# Inverter_3_Phase_MC3PHAC.net
KiCad netlist of a schematic drawn in EAGLE
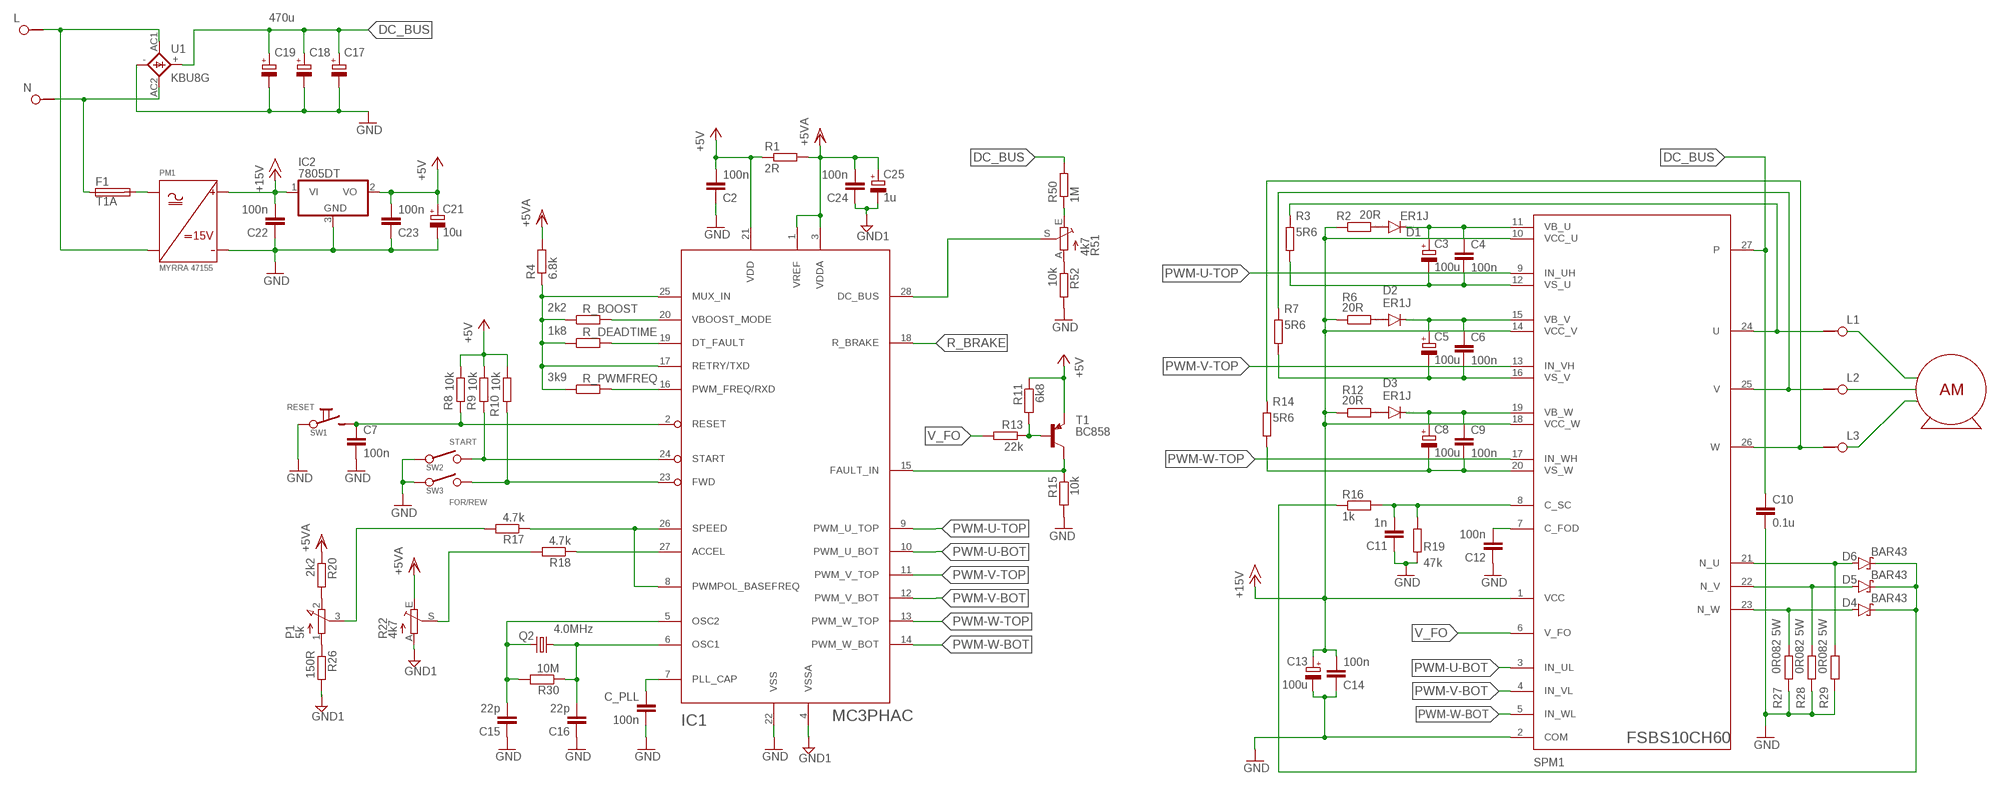
[diagram p0: schematic, sheet 1]

(export (version "E")
  (design (tool "Eeschema 10.0.6"))
  (components
    (comp (ref "C2")
      (value "100n")
      (footprint "eagle-import:C0805")
      (libsource (lib "eagle-import") (part "C-EUC0805"))
    )
    (comp (ref "C3")
      (value "100u")
      (footprint "eagle-import:E2,5-7")
      (libsource (lib "eagle-import") (part "CPOL-EUE2.5-7"))
    )
    (comp (ref "C4")
      (value "100n")
      (footprint "eagle-import:C0805")
      (libsource (lib "eagle-import") (part "C-EUC0805"))
    )
    (comp (ref "C5")
      (value "100u")
      (footprint "eagle-import:E2,5-7")
      (libsource (lib "eagle-import") (part "CPOL-EUE2.5-7"))
    )
    (comp (ref "C6")
      (value "100n")
      (footprint "eagle-import:C0805")
      (libsource (lib "eagle-import") (part "C-EUC0805"))
    )
    (comp (ref "C7")
      (value "100n")
      (footprint "eagle-import:C0805")
      (libsource (lib "eagle-import") (part "C-EUC0805"))
    )
    (comp (ref "C8")
      (value "100u")
      (footprint "eagle-import:E2,5-7")
      (libsource (lib "eagle-import") (part "CPOL-EUE2.5-7"))
    )
    (comp (ref "C9")
      (value "100n")
      (footprint "eagle-import:C0805")
      (libsource (lib "eagle-import") (part "C-EUC0805"))
    )
    (comp (ref "C10")
      (value "0.1u")
      (footprint "eagle-import:C225-074X268")
      (libsource (lib "eagle-import") (part "C-EU225-074X268"))
    )
    (comp (ref "C11")
      (value "1n")
      (footprint "eagle-import:C0805")
      (libsource (lib "eagle-import") (part "C-EUC0805"))
    )
    (comp (ref "C12")
      (value "100n")
      (footprint "eagle-import:C0805")
      (libsource (lib "eagle-import") (part "C-EUC0805"))
    )
    (comp (ref "C13")
      (value "100u")
      (footprint "eagle-import:E2,5-7")
      (libsource (lib "eagle-import") (part "CPOL-EUE2.5-7"))
    )
    (comp (ref "C14")
      (value "100n")
      (footprint "eagle-import:C0805")
      (libsource (lib "eagle-import") (part "C-EUC0805"))
    )
    (comp (ref "C15")
      (value "22p")
      (footprint "eagle-import:C0805")
      (libsource (lib "eagle-import") (part "C-EUC0805"))
    )
    (comp (ref "C16")
      (value "22p")
      (footprint "eagle-import:C0805")
      (libsource (lib "eagle-import") (part "C-EUC0805"))
    )
    (comp (ref "C17")
      (value "470u")
      (footprint "eagle-import:EB35D")
      (libsource (lib "eagle-import") (part "CPOL-EUE10-35"))
    )
    (comp (ref "C18")
      (value "470u")
      (footprint "eagle-import:EB35D")
      (libsource (lib "eagle-import") (part "CPOL-EUE10-35"))
    )
    (comp (ref "C19")
      (value "470u")
      (footprint "eagle-import:EB35D")
      (libsource (lib "eagle-import") (part "CPOL-EUE10-35"))
    )
    (comp (ref "C21")
      (value "10u")
      (footprint "eagle-import:E2,5-7")
      (libsource (lib "eagle-import") (part "CPOL-EUE2.5-7"))
    )
    (comp (ref "C22")
      (value "100n")
      (footprint "eagle-import:C0805")
      (libsource (lib "eagle-import") (part "C-EUC0805"))
    )
    (comp (ref "C23")
      (value "100n")
      (footprint "eagle-import:C0805")
      (libsource (lib "eagle-import") (part "C-EUC0805"))
    )
    (comp (ref "C24")
      (value "100n")
      (footprint "eagle-import:C0805")
      (libsource (lib "eagle-import") (part "C-EUC0805"))
    )
    (comp (ref "C25")
      (value "1u")
      (footprint "eagle-import:E2,5-7")
      (libsource (lib "eagle-import") (part "CPOL-EUE2.5-7"))
    )
    (comp (ref "C_PLL")
      (value "100n")
      (footprint "eagle-import:C0805")
      (libsource (lib "eagle-import") (part "C-EUC0805"))
    )
    (comp (ref "D1")
      (value "ER1J")
      (footprint "eagle-import:DO214AC")
      (libsource (lib "eagle-import") (part "DIODE-DO214AC"))
    )
    (comp (ref "D2")
      (value "ER1J")
      (footprint "eagle-import:DO214AC")
      (libsource (lib "eagle-import") (part "DIODE-DO214AC"))
    )
    (comp (ref "D3")
      (value "ER1J")
      (footprint "eagle-import:DO214AC")
      (libsource (lib "eagle-import") (part "DIODE-DO214AC"))
    )
    (comp (ref "D4")
      (value "BAR43")
      (footprint "eagle-import:SOT23")
      (libsource (lib "eagle-import") (part "BAT54"))
    )
    (comp (ref "D5")
      (value "BAR43")
      (footprint "eagle-import:SOT23")
      (libsource (lib "eagle-import") (part "BAT54"))
    )
    (comp (ref "D6")
      (value "BAR43")
      (footprint "eagle-import:SOT23")
      (libsource (lib "eagle-import") (part "BAT54"))
    )
    (comp (ref "F1")
      (value "T1A")
      (footprint "eagle-import:SH22,5")
      (libsource (lib "eagle-import") (part "FUSESH22,5"))
    )
    (comp (ref "IC1")
      (value "MC3PHAC")
      (footprint "eagle-import:SO28W")
      (libsource (lib "eagle-import") (part "MC3PHAC"))
    )
    (comp (ref "IC2")
      (value "7805DT")
      (footprint "eagle-import:TO252")
      (libsource (lib "eagle-import") (part "78DT05"))
    )
    (comp (ref "L")
      (value "L")
      (footprint "eagle-import:W236-1")
      (libsource (lib "eagle-import") (part "W236-1"))
    )
    (comp (ref "L1")
      (value "L1")
      (footprint "eagle-import:W236-1")
      (libsource (lib "eagle-import") (part "W236-1"))
    )
    (comp (ref "L2")
      (value "L2")
      (footprint "eagle-import:W236-1")
      (libsource (lib "eagle-import") (part "W236-1"))
    )
    (comp (ref "L3")
      (value "L3")
      (footprint "eagle-import:W236-1")
      (libsource (lib "eagle-import") (part "W236-1"))
    )
    (comp (ref "N")
      (value "N")
      (footprint "eagle-import:W236-1")
      (libsource (lib "eagle-import") (part "W236-1"))
    )
    (comp (ref "P1")
      (value "5k")
      (footprint "eagle-import:1X03")
      (libsource (lib "eagle-import") (part "POT"))
    )
    (comp (ref "PM1")
      (value "MYRRA 47155")
      (footprint "eagle-import:MYRRA")
      (libsource (lib "eagle-import") (part "MYRRA"))
    )
    (comp (ref "Q2")
      (value "4.0MHz")
      (footprint "eagle-import:HC49U-V")
      (libsource (lib "eagle-import") (part "CRYSTALHC49U-V"))
    )
    (comp (ref "R1")
      (value "2R")
      (footprint "eagle-import:R1206")
      (libsource (lib "eagle-import") (part "R-EU_R1206"))
    )
    (comp (ref "R2")
      (value "20R")
      (footprint "eagle-import:R1206")
      (libsource (lib "eagle-import") (part "R-EU_R1206"))
    )
    (comp (ref "R3")
      (value "5R6")
      (footprint "eagle-import:M1206")
      (libsource (lib "eagle-import") (part "R-EU_M1206"))
    )
    (comp (ref "R4")
      (value "6.8k")
      (footprint "eagle-import:R0805")
      (libsource (lib "eagle-import") (part "R-EU_R0805"))
    )
    (comp (ref "R6")
      (value "20R")
      (footprint "eagle-import:R1206")
      (libsource (lib "eagle-import") (part "R-EU_R1206"))
    )
    (comp (ref "R7")
      (value "5R6")
      (footprint "eagle-import:M1206")
      (libsource (lib "eagle-import") (part "R-EU_M1206"))
    )
    (comp (ref "R8")
      (value "10k")
      (footprint "eagle-import:R0805")
      (libsource (lib "eagle-import") (part "R-EU_R0805"))
    )
    (comp (ref "R9")
      (value "10k")
      (footprint "eagle-import:R0805")
      (libsource (lib "eagle-import") (part "R-EU_R0805"))
    )
    (comp (ref "R10")
      (value "10k")
      (footprint "eagle-import:R1206")
      (libsource (lib "eagle-import") (part "R-EU_R1206"))
    )
    (comp (ref "R11")
      (value "6k8")
      (footprint "eagle-import:R0805")
      (libsource (lib "eagle-import") (part "R-EU_R0805"))
    )
    (comp (ref "R12")
      (value "20R")
      (footprint "eagle-import:R1206")
      (libsource (lib "eagle-import") (part "R-EU_R1206"))
    )
    (comp (ref "R13")
      (value "22k")
      (footprint "eagle-import:R0805")
      (libsource (lib "eagle-import") (part "R-EU_R0805"))
    )
    (comp (ref "R14")
      (value "5R6")
      (footprint "eagle-import:M1206")
      (libsource (lib "eagle-import") (part "R-EU_M1206"))
    )
    (comp (ref "R15")
      (value "10k")
      (footprint "eagle-import:R0805")
      (libsource (lib "eagle-import") (part "R-EU_R0805"))
    )
    (comp (ref "R16")
      (value "1k")
      (footprint "eagle-import:R0805")
      (libsource (lib "eagle-import") (part "R-EU_R0805"))
    )
    (comp (ref "R17")
      (value "4.7k")
      (footprint "eagle-import:R0805")
      (libsource (lib "eagle-import") (part "R-EU_R0805"))
    )
    (comp (ref "R18")
      (value "4.7k")
      (footprint "eagle-import:R0805")
      (libsource (lib "eagle-import") (part "R-EU_R0805"))
    )
    (comp (ref "R19")
      (value "47k")
      (footprint "eagle-import:R0805")
      (libsource (lib "eagle-import") (part "R-EU_R0805"))
    )
    (comp (ref "R20")
      (value "2k2")
      (footprint "eagle-import:R0805")
      (libsource (lib "eagle-import") (part "R-EU_R0805"))
    )
    (comp (ref "R22")
      (value "4k7")
      (footprint "eagle-import:CA9V")
      (libsource (lib "eagle-import") (part "TRIM_EU-CA9V"))
    )
    (comp (ref "R26")
      (value "150R")
      (footprint "eagle-import:R0805")
      (libsource (lib "eagle-import") (part "R-EU_R0805"))
    )
    (comp (ref "R27")
      (value "0R082 5W")
      (footprint "eagle-import:WSC4527")
      (libsource (lib "eagle-import") (part "R-EU_WSC4527"))
    )
    (comp (ref "R28")
      (value "0R082 5W")
      (footprint "eagle-import:WSC4527")
      (libsource (lib "eagle-import") (part "R-EU_WSC4527"))
    )
    (comp (ref "R29")
      (value "0R082 5W")
      (footprint "eagle-import:WSC4527")
      (libsource (lib "eagle-import") (part "R-EU_WSC4527"))
    )
    (comp (ref "R30")
      (value "10M")
      (footprint "eagle-import:R0805")
      (libsource (lib "eagle-import") (part "R-EU_R0805"))
    )
    (comp (ref "R50")
      (value "1M")
      (footprint "eagle-import:0207_10")
      (libsource (lib "eagle-import") (part "R-EU_0207/10"))
    )
    (comp (ref "R51")
      (value "4k7")
      (footprint "eagle-import:CA9V")
      (libsource (lib "eagle-import") (part "TRIM_EU-CA9V"))
    )
    (comp (ref "R52")
      (value "10k")
      (footprint "eagle-import:R0805")
      (libsource (lib "eagle-import") (part "R-EU_R0805"))
    )
    (comp (ref "R_BOOST")
      (value "2k2")
      (footprint "eagle-import:R0805")
      (libsource (lib "eagle-import") (part "R-EU_R0805"))
    )
    (comp (ref "R_DEADTIME")
      (value "1k8")
      (footprint "eagle-import:R0805")
      (libsource (lib "eagle-import") (part "R-EU_R0805"))
    )
    (comp (ref "R_PWMFREQ")
      (value "3k9")
      (footprint "eagle-import:R0805")
      (libsource (lib "eagle-import") (part "R-EU_R0805"))
    )
    (comp (ref "SPM1")
      (value "FSBS10CH60")
      (footprint "eagle-import:SPM27-BA")
      (libsource (lib "eagle-import") (part "FSBS10CH60"))
    )
    (comp (ref "SW1")
      (value "RESET")
      (footprint "eagle-import:1X02")
      (libsource (lib "eagle-import") (part "BUTTON"))
    )
    (comp (ref "SW2")
      (value "START")
      (footprint "eagle-import:1X02")
      (libsource (lib "eagle-import") (part "SWITCH"))
    )
    (comp (ref "SW3")
      (value "FOR/REW")
      (footprint "eagle-import:1X02")
      (libsource (lib "eagle-import") (part "SWITCH"))
    )
    (comp (ref "T1")
      (value "BC858")
      (footprint "eagle-import:SOT23-BEC")
      (libsource (lib "eagle-import") (part "-PNP-SOT23-BECBC856B"))
    )
    (comp (ref "U1")
      (value "KBU8G")
      (footprint "eagle-import:KBU")
      (libsource (lib "eagle-import") (part "KBU"))
    )
  )
  (nets
    (net (code "1") (name "+5V") (class "Default")
      (node (ref "C2") (pin "2") (pinfunction "2_2") (pintype "passive"))
      (node (ref "C21") (pin "+") (pinfunction "+_+") (pintype "passive"))
      (node (ref "C23") (pin "2") (pinfunction "2_2") (pintype "passive"))
      (node (ref "IC1") (pin "21") (pinfunction "VDD_21") (pintype "power_in"))
      (node (ref "IC2") (pin "2") (pinfunction "VO_2") (pintype "passive"))
      (node (ref "R1") (pin "2") (pinfunction "2_2") (pintype "passive"))
      (node (ref "R10") (pin "1") (pinfunction "1_1") (pintype "passive"))
      (node (ref "R11") (pin "1") (pinfunction "1_1") (pintype "passive"))
      (node (ref "R8") (pin "1") (pinfunction "1_1") (pintype "passive"))
      (node (ref "R9") (pin "1") (pinfunction "1_1") (pintype "passive"))
      (node (ref "T1") (pin "E") (pinfunction "E_E") (pintype "passive"))
    )
    (net (code "2") (name "+5VA") (class "Default")
      (node (ref "C24") (pin "2") (pinfunction "2_2") (pintype "passive"))
      (node (ref "C25") (pin "+") (pinfunction "+_+") (pintype "passive"))
      (node (ref "IC1") (pin "1") (pinfunction "VREF_1") (pintype "input"))
      (node (ref "IC1") (pin "3") (pinfunction "VDDA_3") (pintype "power_in"))
      (node (ref "R1") (pin "1") (pinfunction "1_1") (pintype "passive"))
      (node (ref "R20") (pin "1") (pinfunction "1_1") (pintype "passive"))
      (node (ref "R22") (pin "E") (pinfunction "E_E") (pintype "passive"))
      (node (ref "R4") (pin "2") (pinfunction "2_2") (pintype "passive"))
    )
    (net (code "3") (name "+15V") (class "Default")
      (node (ref "C13") (pin "+") (pinfunction "+_+") (pintype "passive"))
      (node (ref "C14") (pin "2") (pinfunction "2_2") (pintype "passive"))
      (node (ref "C22") (pin "2") (pinfunction "2_2") (pintype "passive"))
      (node (ref "IC2") (pin "1") (pinfunction "VI_1") (pintype "input"))
      (node (ref "PM1") (pin "7") (pinfunction "+VOUT_7") (pintype "power_in"))
      (node (ref "R12") (pin "1") (pinfunction "1_1") (pintype "passive"))
      (node (ref "R2") (pin "1") (pinfunction "1_1") (pintype "passive"))
      (node (ref "R6") (pin "1") (pinfunction "1_1") (pintype "passive"))
      (node (ref "SPM1") (pin "1") (pinfunction "VCC_1") (pintype "passive"))
      (node (ref "SPM1") (pin "10") (pinfunction "VCC_U_10") (pintype "passive"))
      (node (ref "SPM1") (pin "14") (pinfunction "VCC_V_14") (pintype "passive"))
      (node (ref "SPM1") (pin "18") (pinfunction "VCC_W_18") (pintype "passive"))
    )
    (net (code "4") (name "DC_BUS") (class "Default")
      (node (ref "C10") (pin "1") (pinfunction "1_1") (pintype "passive"))
      (node (ref "C17") (pin "+") (pinfunction "+_+") (pintype "passive"))
      (node (ref "C18") (pin "+") (pinfunction "+_+") (pintype "passive"))
      (node (ref "C19") (pin "+") (pinfunction "+_+") (pintype "passive"))
      (node (ref "R50") (pin "2") (pinfunction "2_2") (pintype "passive"))
      (node (ref "SPM1") (pin "27") (pinfunction "P_27") (pintype "passive"))
      (node (ref "U1") (pin "+") (pinfunction "+_+") (pintype "passive"))
    )
    (net (code "5") (name "GND") (class "Default")
      (node (ref "C10") (pin "2") (pinfunction "2_2") (pintype "passive"))
      (node (ref "C11") (pin "1") (pinfunction "1_1") (pintype "passive"))
      (node (ref "C12") (pin "1") (pinfunction "1_1") (pintype "passive"))
      (node (ref "C13") (pin "-") (pinfunction "-_-") (pintype "passive"))
      (node (ref "C14") (pin "1") (pinfunction "1_1") (pintype "passive"))
      (node (ref "C15") (pin "1") (pinfunction "1_1") (pintype "passive"))
      (node (ref "C16") (pin "1") (pinfunction "1_1") (pintype "passive"))
      (node (ref "C17") (pin "-") (pinfunction "-_-") (pintype "passive"))
      (node (ref "C18") (pin "-") (pinfunction "-_-") (pintype "passive"))
      (node (ref "C19") (pin "-") (pinfunction "-_-") (pintype "passive"))
      (node (ref "C2") (pin "1") (pinfunction "1_1") (pintype "passive"))
      (node (ref "C21") (pin "-") (pinfunction "-_-") (pintype "passive"))
      (node (ref "C22") (pin "1") (pinfunction "1_1") (pintype "passive"))
      (node (ref "C23") (pin "1") (pinfunction "1_1") (pintype "passive"))
      (node (ref "C7") (pin "2") (pinfunction "2_2") (pintype "passive"))
      (node (ref "C_PLL") (pin "2") (pinfunction "2_2") (pintype "passive"))
      (node (ref "IC1") (pin "22") (pinfunction "VSS_22") (pintype "power_in"))
      (node (ref "IC2") (pin "3") (pinfunction "GND_3") (pintype "passive"))
      (node (ref "PM1") (pin "9") (pinfunction "-VOUT_9") (pintype "power_in"))
      (node (ref "R15") (pin "2") (pinfunction "2_2") (pintype "passive"))
      (node (ref "R19") (pin "2") (pinfunction "2_2") (pintype "passive"))
      (node (ref "R27") (pin "1") (pinfunction "1_1") (pintype "passive"))
      (node (ref "R28") (pin "1") (pinfunction "1_1") (pintype "passive"))
      (node (ref "R29") (pin "1") (pinfunction "1_1") (pintype "passive"))
      (node (ref "R52") (pin "2") (pinfunction "2_2") (pintype "passive"))
      (node (ref "SPM1") (pin "2") (pinfunction "COM_2") (pintype "passive"))
      (node (ref "SW1") (pin "1") (pinfunction "P$1_1") (pintype "passive"))
      (node (ref "SW2") (pin "1") (pinfunction "P$1_1") (pintype "passive"))
      (node (ref "SW3") (pin "1") (pinfunction "P$1_1") (pintype "passive"))
      (node (ref "U1") (pin "-") (pinfunction "-_-") (pintype "passive"))
    )
    (net (code "6") (name "GND1") (class "Default")
      (node (ref "C24") (pin "1") (pinfunction "1_1") (pintype "passive"))
      (node (ref "C25") (pin "-") (pinfunction "-_-") (pintype "passive"))
      (node (ref "IC1") (pin "4") (pinfunction "VSSA_4") (pintype "power_in"))
      (node (ref "R22") (pin "A") (pinfunction "A_A") (pintype "passive"))
      (node (ref "R26") (pin "2") (pinfunction "2_2") (pintype "passive"))
    )
    (net (code "7") (name "Net-(D1-PadA)") (class "Default")
      (node (ref "D1") (pin "A") (pinfunction "A_A") (pintype "passive"))
      (node (ref "R2") (pin "2") (pinfunction "2_2") (pintype "passive"))
    )
    (net (code "8") (name "Net-(D2-PadA)") (class "Default")
      (node (ref "D2") (pin "A") (pinfunction "A_A") (pintype "passive"))
      (node (ref "R6") (pin "2") (pinfunction "2_2") (pintype "passive"))
    )
    (net (code "9") (name "Net-(D3-PadA)") (class "Default")
      (node (ref "D3") (pin "A") (pinfunction "A_A") (pintype "passive"))
      (node (ref "R12") (pin "2") (pinfunction "2_2") (pintype "passive"))
    )
    (net (code "10") (name "Net-(D4-A)") (class "Default")
      (node (ref "D4") (pin "1") (pinfunction "A_1") (pintype "passive"))
      (node (ref "R27") (pin "2") (pinfunction "2_2") (pintype "passive"))
      (node (ref "SPM1") (pin "23") (pinfunction "N_W_23") (pintype "passive"))
    )
    (net (code "11") (name "Net-(D4-C)") (class "Default")
      (node (ref "D4") (pin "3") (pinfunction "C_3") (pintype "passive"))
      (node (ref "D5") (pin "3") (pinfunction "C_3") (pintype "passive"))
      (node (ref "D6") (pin "3") (pinfunction "C_3") (pintype "passive"))
      (node (ref "R16") (pin "1") (pinfunction "1_1") (pintype "passive"))
    )
    (net (code "12") (name "Net-(D5-A)") (class "Default")
      (node (ref "D5") (pin "1") (pinfunction "A_1") (pintype "passive"))
      (node (ref "R28") (pin "2") (pinfunction "2_2") (pintype "passive"))
      (node (ref "SPM1") (pin "22") (pinfunction "N_V_22") (pintype "passive"))
    )
    (net (code "13") (name "Net-(D6-A)") (class "Default")
      (node (ref "D6") (pin "1") (pinfunction "A_1") (pintype "passive"))
      (node (ref "R29") (pin "2") (pinfunction "2_2") (pintype "passive"))
      (node (ref "SPM1") (pin "21") (pinfunction "N_U_21") (pintype "passive"))
    )
    (net (code "14") (name "Net-(IC1-ACCEL)") (class "Default")
      (node (ref "IC1") (pin "27") (pinfunction "ACCEL_27") (pintype "bidirectional"))
      (node (ref "R18") (pin "1") (pinfunction "1_1") (pintype "passive"))
    )
    (net (code "15") (name "Net-(IC1-DC_BUS)") (class "Default")
      (node (ref "IC1") (pin "28") (pinfunction "DC_BUS_28") (pintype "bidirectional"))
      (node (ref "R51") (pin "S") (pinfunction "S_S") (pintype "passive"))
    )
    (net (code "16") (name "Net-(IC1-DT_FAULT)") (class "Default")
      (node (ref "IC1") (pin "19") (pinfunction "DT_FAULT_19") (pintype "input"))
      (node (ref "R_DEADTIME") (pin "2") (pinfunction "2_2") (pintype "passive"))
    )
    (net (code "17") (name "Net-(IC1-FAULT_IN)") (class "Default")
      (node (ref "IC1") (pin "15") (pinfunction "FAULT_IN_15") (pintype "bidirectional"))
      (node (ref "R15") (pin "1") (pinfunction "1_1") (pintype "passive"))
      (node (ref "T1") (pin "C") (pinfunction "C_C") (pintype "passive"))
    )
    (net (code "18") (name "Net-(IC1-FWD)") (class "Default")
      (node (ref "IC1") (pin "23") (pinfunction "FWD_23") (pintype "input"))
      (node (ref "R10") (pin "2") (pinfunction "2_2") (pintype "passive"))
      (node (ref "SW3") (pin "2") (pinfunction "P$3_2") (pintype "passive"))
    )
    (net (code "19") (name "Net-(IC1-MUX_IN)") (class "Default")
      (node (ref "IC1") (pin "17") (pinfunction "RETRY/TXD_17") (pintype "bidirectional"))
      (node (ref "IC1") (pin "25") (pinfunction "MUX_IN_25") (pintype "bidirectional"))
      (node (ref "R4") (pin "1") (pinfunction "1_1") (pintype "passive"))
      (node (ref "R_BOOST") (pin "1") (pinfunction "1_1") (pintype "passive"))
      (node (ref "R_DEADTIME") (pin "1") (pinfunction "1_1") (pintype "passive"))
      (node (ref "R_PWMFREQ") (pin "1") (pinfunction "1_1") (pintype "passive"))
    )
    (net (code "20") (name "Net-(IC1-OSC1)") (class "Default")
      (node (ref "C16") (pin "2") (pinfunction "2_2") (pintype "passive"))
      (node (ref "IC1") (pin "6") (pinfunction "OSC1_6") (pintype "passive"))
      (node (ref "Q2") (pin "1") (pinfunction "1_1") (pintype "passive"))
      (node (ref "R30") (pin "1") (pinfunction "1_1") (pintype "passive"))
    )
    (net (code "21") (name "Net-(IC1-OSC2)") (class "Default")
      (node (ref "C15") (pin "2") (pinfunction "2_2") (pintype "passive"))
      (node (ref "IC1") (pin "5") (pinfunction "OSC2_5") (pintype "passive"))
      (node (ref "Q2") (pin "2") (pinfunction "2_2") (pintype "passive"))
      (node (ref "R30") (pin "2") (pinfunction "2_2") (pintype "passive"))
    )
    (net (code "22") (name "Net-(IC1-PLL_CAP)") (class "Default")
      (node (ref "C_PLL") (pin "1") (pinfunction "1_1") (pintype "passive"))
      (node (ref "IC1") (pin "7") (pinfunction "PLL_CAP_7") (pintype "passive"))
    )
    (net (code "23") (name "Net-(IC1-PWMPOL_BASEFREQ)") (class "Default")
      (node (ref "IC1") (pin "26") (pinfunction "SPEED_26") (pintype "bidirectional"))
      (node (ref "IC1") (pin "8") (pinfunction "PWMPOL_BASEFREQ_8") (pintype "bidirectional"))
      (node (ref "R17") (pin "1") (pinfunction "1_1") (pintype "passive"))
    )
    (net (code "24") (name "Net-(IC1-PWM_FREQ{slash}RXD)") (class "Default")
      (node (ref "IC1") (pin "16") (pinfunction "PWM_FREQ/RXD_16") (pintype "bidirectional"))
      (node (ref "R_PWMFREQ") (pin "2") (pinfunction "2_2") (pintype "passive"))
    )
    (net (code "25") (name "Net-(IC1-RESET)") (class "Default")
      (node (ref "C7") (pin "1") (pinfunction "1_1") (pintype "passive"))
      (node (ref "IC1") (pin "2") (pinfunction "RESET_2") (pintype "input"))
      (node (ref "R8") (pin "2") (pinfunction "2_2") (pintype "passive"))
      (node (ref "SW1") (pin "2") (pinfunction "P$2_2") (pintype "passive"))
    )
    (net (code "26") (name "Net-(IC1-START)") (class "Default")
      (node (ref "IC1") (pin "24") (pinfunction "START_24") (pintype "input"))
      (node (ref "R9") (pin "2") (pinfunction "2_2") (pintype "passive"))
      (node (ref "SW2") (pin "2") (pinfunction "P$3_2") (pintype "passive"))
    )
    (net (code "27") (name "Net-(IC1-VBOOST_MODE)") (class "Default")
      (node (ref "IC1") (pin "20") (pinfunction "VBOOST_MODE_20") (pintype "bidirectional"))
      (node (ref "R_BOOST") (pin "2") (pinfunction "2_2") (pintype "passive"))
    )
    (net (code "28") (name "Net-(L-KL1)") (class "Default")
      (node (ref "L") (pin "1") (pinfunction "KL1_1") (pintype "passive"))
      (node (ref "PM1") (pin "1") (pinfunction "ACIN2_1") (pintype "power_in"))
      (node (ref "U1") (pin "AC1") (pinfunction "AC1_AC1") (pintype "passive"))
    )
    (net (code "29") (name "Net-(L1-KL1)") (class "Default")
      (node (ref "L1") (pin "1") (pinfunction "KL1_1") (pintype "passive"))
      (node (ref "R3") (pin "1") (pinfunction "1_1") (pintype "passive"))
      (node (ref "SPM1") (pin "24") (pinfunction "U_24") (pintype "passive"))
    )
    (net (code "30") (name "Net-(L2-KL1)") (class "Default")
      (node (ref "L2") (pin "1") (pinfunction "KL1_1") (pintype "passive"))
      (node (ref "R7") (pin "1") (pinfunction "1_1") (pintype "passive"))
      (node (ref "SPM1") (pin "25") (pinfunction "V_25") (pintype "passive"))
    )
    (net (code "31") (name "Net-(L3-KL1)") (class "Default")
      (node (ref "L3") (pin "1") (pinfunction "KL1_1") (pintype "passive"))
      (node (ref "R14") (pin "1") (pinfunction "1_1") (pintype "passive"))
      (node (ref "SPM1") (pin "26") (pinfunction "W_26") (pintype "passive"))
    )
    (net (code "32") (name "Net-(N-KL1)") (class "Default")
      (node (ref "F1") (pin "1") (pinfunction "1_1") (pintype "passive"))
      (node (ref "N") (pin "1") (pinfunction "KL1_1") (pintype "passive"))
      (node (ref "U1") (pin "AC2") (pinfunction "AC2_AC2") (pintype "passive"))
    )
    (net (code "33") (name "Net-(P1-A)") (class "Default")
      (node (ref "P1") (pin "1") (pinfunction "A_1") (pintype "passive"))
      (node (ref "R26") (pin "1") (pinfunction "1_1") (pintype "passive"))
    )
    (net (code "34") (name "Net-(P1-E)") (class "Default")
      (node (ref "P1") (pin "2") (pinfunction "E_2") (pintype "passive"))
      (node (ref "R20") (pin "2") (pinfunction "2_2") (pintype "passive"))
    )
    (net (code "35") (name "Net-(P1-S)") (class "Default")
      (node (ref "P1") (pin "3") (pinfunction "S_3") (pintype "passive"))
      (node (ref "R17") (pin "2") (pinfunction "2_2") (pintype "passive"))
    )
    (net (code "36") (name "Net-(PM1-ACIN1)") (class "Default")
      (node (ref "F1") (pin "2") (pinfunction "2_2") (pintype "passive"))
      (node (ref "PM1") (pin "5") (pinfunction "ACIN1_5") (pintype "power_in"))
    )
    (net (code "37") (name "Net-(R11-Pad2)") (class "Default")
      (node (ref "R11") (pin "2") (pinfunction "2_2") (pintype "passive"))
      (node (ref "R13") (pin "1") (pinfunction "1_1") (pintype "passive"))
      (node (ref "T1") (pin "B") (pinfunction "B_B") (pintype "passive"))
    )
    (net (code "38") (name "Net-(R18-Pad2)") (class "Default")
      (node (ref "R18") (pin "2") (pinfunction "2_2") (pintype "passive"))
      (node (ref "R22") (pin "S") (pinfunction "S_S") (pintype "passive"))
    )
    (net (code "39") (name "Net-(R50-Pad1)") (class "Default")
      (node (ref "R50") (pin "1") (pinfunction "1_1") (pintype "passive"))
      (node (ref "R51") (pin "E") (pinfunction "E_E") (pintype "passive"))
    )
    (net (code "40") (name "Net-(R51-PadA)") (class "Default")
      (node (ref "R51") (pin "A") (pinfunction "A_A") (pintype "passive"))
      (node (ref "R52") (pin "1") (pinfunction "1_1") (pintype "passive"))
    )
    (net (code "41") (name "Net-(SPM1-C_FOD)") (class "Default")
      (node (ref "C12") (pin "2") (pinfunction "2_2") (pintype "passive"))
      (node (ref "SPM1") (pin "7") (pinfunction "C_FOD_7") (pintype "passive"))
    )
    (net (code "42") (name "Net-(SPM1-C_SC)") (class "Default")
      (node (ref "C11") (pin "2") (pinfunction "2_2") (pintype "passive"))
      (node (ref "R16") (pin "2") (pinfunction "2_2") (pintype "passive"))
      (node (ref "R19") (pin "1") (pinfunction "1_1") (pintype "passive"))
      (node (ref "SPM1") (pin "8") (pinfunction "C_SC_8") (pintype "passive"))
    )
    (net (code "43") (name "Net-(SPM1-VB_U)") (class "Default")
      (node (ref "C3") (pin "+") (pinfunction "+_+") (pintype "passive"))
      (node (ref "C4") (pin "1") (pinfunction "1_1") (pintype "passive"))
      (node (ref "D1") (pin "C") (pinfunction "C_C") (pintype "passive"))
      (node (ref "SPM1") (pin "11") (pinfunction "VB_U_11") (pintype "passive"))
    )
    (net (code "44") (name "Net-(SPM1-VB_V)") (class "Default")
      (node (ref "C5") (pin "+") (pinfunction "+_+") (pintype "passive"))
      (node (ref "C6") (pin "1") (pinfunction "1_1") (pintype "passive"))
      (node (ref "D2") (pin "C") (pinfunction "C_C") (pintype "passive"))
      (node (ref "SPM1") (pin "15") (pinfunction "VB_V_15") (pintype "passive"))
    )
    (net (code "45") (name "Net-(SPM1-VB_W)") (class "Default")
      (node (ref "C8") (pin "+") (pinfunction "+_+") (pintype "passive"))
      (node (ref "C9") (pin "1") (pinfunction "1_1") (pintype "passive"))
      (node (ref "D3") (pin "C") (pinfunction "C_C") (pintype "passive"))
      (node (ref "SPM1") (pin "19") (pinfunction "VB_W_19") (pintype "passive"))
    )
    (net (code "46") (name "Net-(SPM1-VS_U)") (class "Default")
      (node (ref "C3") (pin "-") (pinfunction "-_-") (pintype "passive"))
      (node (ref "C4") (pin "2") (pinfunction "2_2") (pintype "passive"))
      (node (ref "R3") (pin "2") (pinfunction "2_2") (pintype "passive"))
      (node (ref "SPM1") (pin "12") (pinfunction "VS_U_12") (pintype "passive"))
    )
    (net (code "47") (name "Net-(SPM1-VS_V)") (class "Default")
      (node (ref "C5") (pin "-") (pinfunction "-_-") (pintype "passive"))
      (node (ref "C6") (pin "2") (pinfunction "2_2") (pintype "passive"))
      (node (ref "R7") (pin "2") (pinfunction "2_2") (pintype "passive"))
      (node (ref "SPM1") (pin "16") (pinfunction "VS_V_16") (pintype "passive"))
    )
    (net (code "48") (name "Net-(SPM1-VS_W)") (class "Default")
      (node (ref "C8") (pin "-") (pinfunction "-_-") (pintype "passive"))
      (node (ref "C9") (pin "2") (pinfunction "2_2") (pintype "passive"))
      (node (ref "R14") (pin "2") (pinfunction "2_2") (pintype "passive"))
      (node (ref "SPM1") (pin "20") (pinfunction "VS_W_20") (pintype "passive"))
    )
    (net (code "49") (name "PWM-U-BOT") (class "Default")
      (node (ref "IC1") (pin "10") (pinfunction "PWM_U_BOT_10") (pintype "output"))
      (node (ref "SPM1") (pin "3") (pinfunction "IN_UL_3") (pintype "passive"))
    )
    (net (code "50") (name "PWM-U-TOP") (class "Default")
      (node (ref "IC1") (pin "9") (pinfunction "PWM_U_TOP_9") (pintype "output"))
      (node (ref "SPM1") (pin "9") (pinfunction "IN_UH_9") (pintype "passive"))
    )
    (net (code "51") (name "PWM-V-BOT") (class "Default")
      (node (ref "IC1") (pin "12") (pinfunction "PWM_V_BOT_12") (pintype "output"))
      (node (ref "SPM1") (pin "4") (pinfunction "IN_VL_4") (pintype "passive"))
    )
    (net (code "52") (name "PWM-V-TOP") (class "Default")
      (node (ref "IC1") (pin "11") (pinfunction "PWM_V_TOP_11") (pintype "output"))
      (node (ref "SPM1") (pin "13") (pinfunction "IN_VH_13") (pintype "passive"))
    )
    (net (code "53") (name "PWM-W-BOT") (class "Default")
      (node (ref "IC1") (pin "14") (pinfunction "PWM_W_BOT_14") (pintype "output"))
      (node (ref "SPM1") (pin "5") (pinfunction "IN_WL_5") (pintype "passive"))
    )
    (net (code "54") (name "PWM-W-TOP") (class "Default")
      (node (ref "IC1") (pin "13") (pinfunction "PWM_W_TOP_13") (pintype "output"))
      (node (ref "SPM1") (pin "17") (pinfunction "IN_WH_17") (pintype "passive"))
    )
    (net (code "55") (name "R_BRAKE") (class "Default")
      (node (ref "IC1") (pin "18") (pinfunction "R_BRAKE_18") (pintype "output"))
    )
    (net (code "56") (name "V_FO") (class "Default")
      (node (ref "R13") (pin "2") (pinfunction "2_2") (pintype "passive"))
      (node (ref "SPM1") (pin "6") (pinfunction "V_FO_6") (pintype "passive"))
    )
    (net (code "60") (name "unconnected-(L-KL2-Pad2)") (class "Default")
      (node (ref "L") (pin "2") (pinfunction "KL2_2") (pintype "passive"))
    )
    (net (code "61") (name "unconnected-(L1-KL2-Pad2)") (class "Default")
      (node (ref "L1") (pin "2") (pinfunction "KL2_2") (pintype "passive"))
    )
    (net (code "62") (name "unconnected-(L2-KL2-Pad2)") (class "Default")
      (node (ref "L2") (pin "2") (pinfunction "KL2_2") (pintype "passive"))
    )
    (net (code "63") (name "unconnected-(L3-KL2-Pad2)") (class "Default")
      (node (ref "L3") (pin "2") (pinfunction "KL2_2") (pintype "passive"))
    )
    (net (code "64") (name "unconnected-(N-KL2-Pad2)") (class "Default")
      (node (ref "N") (pin "2") (pinfunction "KL2_2") (pintype "passive"))
    )
  )
)
